# Power.net
KiCad netlist of a schematic drawn in Altium Designer
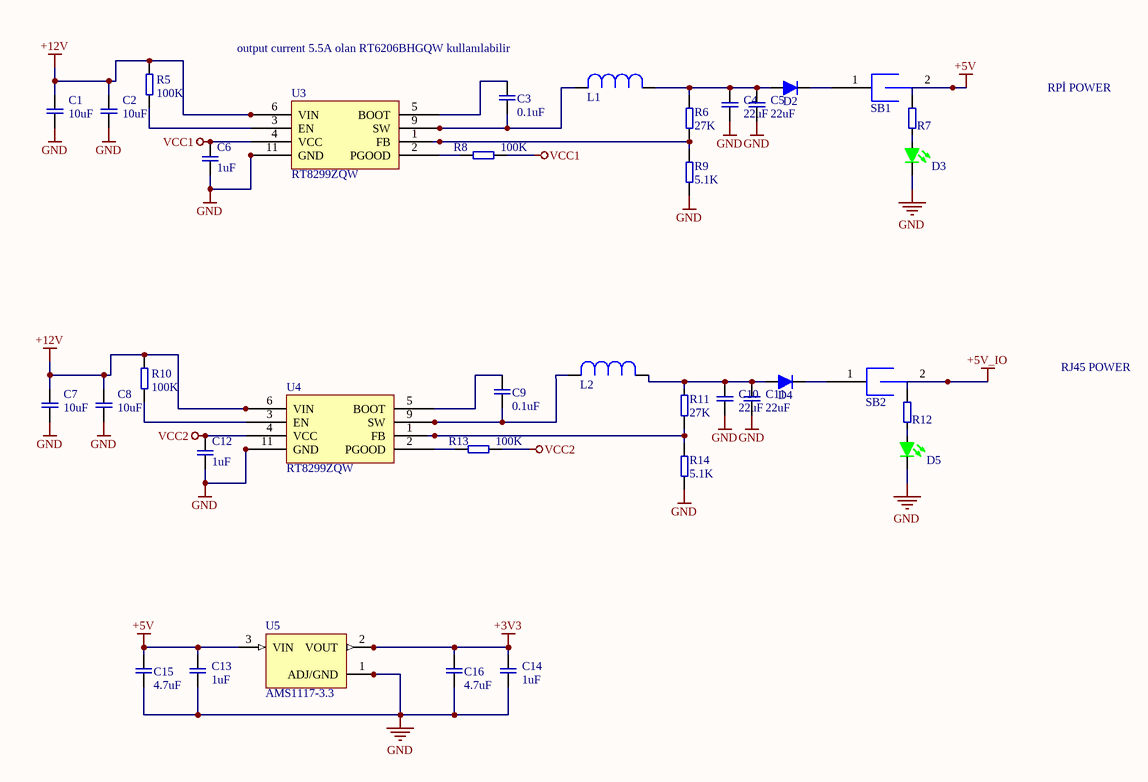
[diagram p0: Power.SchDoc]

(export (version "E")
  (design (tool "Eeschema 10.0.6"))
  (components
    (comp (ref "C1")
      (value "10uF")
      (footprint "C0805")
      (description "CAP CER 10UF 25V X5R 0805")
      (fields (field (name "PART NUMBER") "CC0805KKX5R8BB106") (field (name "VOLTAGE") "25V"))
      (libsource (lib "anayurt") (part "CAP"))
    )
    (comp (ref "C2")
      (value "10uF")
      (footprint "C0805")
      (description "CAP CER 10UF 25V X5R 0805")
      (fields (field (name "PART NUMBER") "CC0805KKX5R8BB106") (field (name "VOLTAGE") "25V"))
      (libsource (lib "anayurt") (part "CAP"))
    )
    (comp (ref "C3")
      (value "0.1uF")
      (footprint "C0402")
      (description "CAP CER 0.1UF 25V X7R 0402")
      (fields (field (name "PART NUMBER") "04023C104KAT2A") (field (name "VOLTAGE") "25V"))
      (libsource (lib "anayurt") (part "CAP"))
    )
    (comp (ref "C4")
      (value "22uF")
      (footprint "C1210")
      (description "CAP CER 22UF 25V X5R 1210")
      (fields (field (name "PART NUMBER") "CL32A226KAJNNWE") (field (name "VOLTAGE") "25V"))
      (libsource (lib "anayurt") (part "CAP"))
    )
    (comp (ref "C5")
      (value "22uF")
      (footprint "C1210")
      (description "CAP CER 22UF 25V X5R 1210")
      (fields (field (name "PART NUMBER") "CL32A226KAJNNWE") (field (name "VOLTAGE") "25V"))
      (libsource (lib "anayurt") (part "CAP"))
    )
    (comp (ref "C6")
      (value "1uF")
      (footprint "C0603")
      (description "CAP CER 1UF 25V X7R 0603")
      (fields (field (name "PART NUMBER") "CGA3E1X7R1E105M080AC") (field (name "VOLTAGE") "25V"))
      (libsource (lib "anayurt") (part "CAP"))
    )
    (comp (ref "C7")
      (value "10uF")
      (footprint "C0805")
      (description "CAP CER 10UF 25V X5R 0805")
      (fields (field (name "PART NUMBER") "CC0805KKX5R8BB106") (field (name "VOLTAGE") "25V"))
      (libsource (lib "anayurt") (part "CAP"))
    )
    (comp (ref "C8")
      (value "10uF")
      (footprint "C0805")
      (description "CAP CER 10UF 25V X5R 0805")
      (fields (field (name "PART NUMBER") "CC0805KKX5R8BB106") (field (name "VOLTAGE") "25V"))
      (libsource (lib "anayurt") (part "CAP"))
    )
    (comp (ref "C9")
      (value "0.1uF")
      (footprint "C0402")
      (description "CAP CER 0.1UF 25V X7R 0402")
      (fields (field (name "PART NUMBER") "04023C104KAT2A") (field (name "VOLTAGE") "25V"))
      (libsource (lib "anayurt") (part "CAP"))
    )
    (comp (ref "C10")
      (value "22uF")
      (footprint "C1210")
      (description "CAP CER 22UF 25V X5R 1210")
      (fields (field (name "PART NUMBER") "CL32A226KAJNNWE") (field (name "VOLTAGE") "25V"))
      (libsource (lib "anayurt") (part "CAP"))
    )
    (comp (ref "C11")
      (value "22uF")
      (footprint "C1210")
      (description "CAP CER 22UF 25V X5R 1210")
      (fields (field (name "PART NUMBER") "CL32A226KAJNNWE") (field (name "VOLTAGE") "25V"))
      (libsource (lib "anayurt") (part "CAP"))
    )
    (comp (ref "C12")
      (value "1uF")
      (footprint "C0603")
      (description "CAP CER 1UF 25V X7R 0603")
      (fields (field (name "PART NUMBER") "CGA3E1X7R1E105M080AC") (field (name "VOLTAGE") "25V"))
      (libsource (lib "anayurt") (part "CAP"))
    )
    (comp (ref "C13")
      (value "1uF")
      (footprint "C0402")
      (description "CAP CER 1UF 16V X5R 0402")
      (fields (field (name "PART NUMBER") "CL05A105KO5NNNC") (field (name "VOLTAGE") "16V"))
      (libsource (lib "anayurt") (part "CAP"))
    )
    (comp (ref "C14")
      (value "1uF")
      (footprint "C0402")
      (description "CAP CER 1UF 16V X5R 0402")
      (fields (field (name "PART NUMBER") "CL05A105KO5NNNC") (field (name "VOLTAGE") "16V"))
      (libsource (lib "anayurt") (part "CAP"))
    )
    (comp (ref "C15")
      (value "4.7uF")
      (footprint "C0402")
      (description "CAP CER 4.7UF 10V X5R 0402")
      (fields (field (name "PART NUMBER") "C1005X5R1A475K050BC") (field (name "VOLTAGE") "10V"))
      (libsource (lib "anayurt") (part "CAP"))
    )
    (comp (ref "C16")
      (value "4.7uF")
      (footprint "C0402")
      (description "CAP CER 4.7UF 10V X5R 0402")
      (fields (field (name "PART NUMBER") "C1005X5R1A475K050BC") (field (name "VOLTAGE") "10V"))
      (libsource (lib "anayurt") (part "CAP"))
    )
    (comp (ref "D2")
      (value "TSSA3U60 R3G")
      (footprint "TAIWAN_TSSA3U60 R3G")
      (description "DIODE SCHOTTKY 60V 3A DO214AC")
      (fields (field (name "MANUFACTURER") "Taiwan Semiconductor Corporation"))
      (libsource (lib "anayurt") (part "DIODE"))
    )
    (comp (ref "D3")
      (value "SML-LX0603GW-TR")
      (footprint "L0603")
      (description "LED GREEN DIFFUSED SMD")
      (fields (field (name "MANUFACTURER") "Lumex Opto/Components Inc."))
      (libsource (lib "anayurt") (part "LED_GREEN"))
    )
    (comp (ref "D4")
      (value "TSSA3U60 R3G")
      (footprint "TAIWAN_TSSA3U60 R3G")
      (description "DIODE SCHOTTKY 60V 3A DO214AC")
      (fields (field (name "MANUFACTURER") "Taiwan Semiconductor Corporation"))
      (libsource (lib "anayurt") (part "DIODE"))
    )
    (comp (ref "D5")
      (value "SML-LX0603GW-TR")
      (footprint "L0603")
      (description "LED GREEN DIFFUSED SMD")
      (fields (field (name "MANUFACTURER") "Lumex Opto/Components Inc."))
      (libsource (lib "anayurt") (part "LED_GREEN"))
    )
    (comp (ref "L1")
      (value "XAL6060-682MEB")
      (footprint "CC_XAL6060-682MEB")
      (description "6.8uH 9A 20.8mOhm Inductor")
      (fields (field (name "MANUFACTURER") "Coilcraft"))
      (libsource (lib "anayurt") (part "PINDC"))
    )
    (comp (ref "L2")
      (value "XAL6060-682MEB")
      (footprint "CC_XAL6060-682MEB")
      (description "6.8uH 9A 20.8mOhm Inductor")
      (fields (field (name "MANUFACTURER") "Coilcraft"))
      (libsource (lib "anayurt") (part "PINDC"))
    )
    (comp (ref "R5")
      (value "100K")
      (footprint "R0402")
      (description "RES SMD 100K OHM 1% 1/16W 0402")
      (fields (field (name "PART NUMBER") "RC0402FR-07100KL") (field (name "TOLERANCE") "1%"))
      (libsource (lib "anayurt") (part "RES"))
    )
    (comp (ref "R6")
      (value "27K")
      (footprint "R0402")
      (description "RES 27K OHM 1% 1/16W 0402")
      (fields (field (name "PART NUMBER") "RMCF0402FT27K0") (field (name "TOLERANCE") "±1%"))
      (libsource (lib "anayurt") (part "RES"))
    )
    (comp (ref "R7")
      (value "330R")
      (footprint "R0603")
      (description "RES 330 OHM 1% 1/10W 0603")
      (fields (field (name "PART NUMBER") "RMCF0603FT330R") (field (name "TOLERANCE") "0.1%"))
      (libsource (lib "anayurt") (part "RES"))
    )
    (comp (ref "R8")
      (value "100K")
      (footprint "R0402")
      (description "RES SMD 100K OHM 1% 1/16W 0402")
      (fields (field (name "PART NUMBER") "RC0402FR-07100KL") (field (name "TOLERANCE") "1%"))
      (libsource (lib "anayurt") (part "RES"))
    )
    (comp (ref "R9")
      (value "5.1K")
      (footprint "R0402")
      (description "RES 5.1K OHM 1% 1/16W 0402")
      (fields (field (name "PART NUMBER") "RC0402FR-075K1L") (field (name "TOLERANCE") "1%"))
      (libsource (lib "anayurt") (part "RES"))
    )
    (comp (ref "R10")
      (value "100K")
      (footprint "R0402")
      (description "RES SMD 100K OHM 1% 1/16W 0402")
      (fields (field (name "PART NUMBER") "RC0402FR-07100KL") (field (name "TOLERANCE") "1%"))
      (libsource (lib "anayurt") (part "RES"))
    )
    (comp (ref "R11")
      (value "27K")
      (footprint "R0402")
      (description "RES 27K OHM 1% 1/16W 0402")
      (fields (field (name "PART NUMBER") "RMCF0402FT27K0") (field (name "TOLERANCE") "±1%"))
      (libsource (lib "anayurt") (part "RES"))
    )
    (comp (ref "R12")
      (value "330R")
      (footprint "R0603")
      (description "RES 330 OHM 1% 1/10W 0603")
      (fields (field (name "PART NUMBER") "RMCF0603FT330R") (field (name "TOLERANCE") "0.1%"))
      (libsource (lib "anayurt") (part "RES"))
    )
    (comp (ref "R13")
      (value "100K")
      (footprint "R0402")
      (description "RES SMD 100K OHM 1% 1/16W 0402")
      (fields (field (name "PART NUMBER") "RC0402FR-07100KL") (field (name "TOLERANCE") "1%"))
      (libsource (lib "anayurt") (part "RES"))
    )
    (comp (ref "R14")
      (value "5.1K")
      (footprint "R0402")
      (description "RES 5.1K OHM 1% 1/16W 0402")
      (fields (field (name "PART NUMBER") "RC0402FR-075K1L") (field (name "TOLERANCE") "1%"))
      (libsource (lib "anayurt") (part "RES"))
    )
    (comp (ref "SB1")
      (value "Jumper")
      (footprint "SB.0805")
      (description "0805 Solder Bridge")
      (fields (field (name "PART NUMBER") "Solder Bridge0805"))
      (libsource (lib "anayurt") (part "Bridge"))
    )
    (comp (ref "SB2")
      (value "Jumper")
      (footprint "SB.0805")
      (description "0805 Solder Bridge")
      (fields (field (name "PART NUMBER") "Solder Bridge0805"))
      (libsource (lib "anayurt") (part "Bridge"))
    )
    (comp (ref "U3")
      (value "RT8299ZQW")
      (footprint "RT8299ZQW")
      (description "IC REG BUCK ADJUSTABLE 3A 10WDFN")
      (fields (field (name "MANUFACTURER") "Richtek USA Inc."))
      (libsource (lib "anayurt") (part "RT8299ZQW"))
    )
    (comp (ref "U4")
      (value "RT8299ZQW")
      (footprint "RT8299ZQW")
      (description "IC REG BUCK ADJUSTABLE 3A 10WDFN")
      (fields (field (name "MANUFACTURER") "Richtek USA Inc."))
      (libsource (lib "anayurt") (part "RT8299ZQW"))
    )
    (comp (ref "U5")
      (value "AMS1117-3.3")
      (footprint "AMS1117-3.3")
      (description "IC-1117 V.REG. 1A 3V3 SOT223 SMD AMS")
      (fields (field (name "MANUFACTURER") "AMS"))
      (libsource (lib "anayurt") (part "AMS1117-3.3"))
    )
  )
  (nets
    (net (code "1") (name "+3V3") (class "Default")
      (node (ref "C14") (pin "2") (pinfunction "2_2") (pintype "passive"))
      (node (ref "C16") (pin "2") (pinfunction "2_2") (pintype "passive"))
      (node (ref "U5") (pin "2") (pinfunction "VOUT_2") (pintype "output"))
    )
    (net (code "2") (name "+5V") (class "Default")
      (node (ref "C13") (pin "2") (pinfunction "2_2") (pintype "passive"))
      (node (ref "C15") (pin "2") (pinfunction "2_2") (pintype "passive"))
      (node (ref "R7") (pin "2") (pinfunction "2_2") (pintype "passive"))
      (node (ref "SB1") (pin "2") (pinfunction "2_2") (pintype "passive"))
      (node (ref "U5") (pin "3") (pinfunction "VIN_3") (pintype "input"))
    )
    (net (code "3") (name "+5V_IO") (class "Default")
      (node (ref "R12") (pin "2") (pinfunction "2_2") (pintype "passive"))
      (node (ref "SB2") (pin "2") (pinfunction "2_2") (pintype "passive"))
    )
    (net (code "4") (name "+12V") (class "Default")
      (node (ref "C1") (pin "1") (pinfunction "1_1") (pintype "passive"))
      (node (ref "C2") (pin "1") (pinfunction "1_1") (pintype "passive"))
      (node (ref "C7") (pin "1") (pinfunction "1_1") (pintype "passive"))
      (node (ref "C8") (pin "1") (pinfunction "1_1") (pintype "passive"))
      (node (ref "R10") (pin "2") (pinfunction "2_2") (pintype "passive"))
      (node (ref "R5") (pin "2") (pinfunction "2_2") (pintype "passive"))
      (node (ref "U3") (pin "6") (pinfunction "VIN_6") (pintype "passive"))
      (node (ref "U3") (pin "7") (pinfunction "VIN_7") (pintype "passive"))
      (node (ref "U4") (pin "6") (pinfunction "VIN_6") (pintype "passive"))
      (node (ref "U4") (pin "7") (pinfunction "VIN_7") (pintype "passive"))
    )
    (net (code "5") (name "GND") (class "Default")
      (node (ref "C1") (pin "2") (pinfunction "2_2") (pintype "passive"))
      (node (ref "C10") (pin "1") (pinfunction "1_1") (pintype "passive"))
      (node (ref "C11") (pin "1") (pinfunction "1_1") (pintype "passive"))
      (node (ref "C12") (pin "1") (pinfunction "1_1") (pintype "passive"))
      (node (ref "C13") (pin "1") (pinfunction "1_1") (pintype "passive"))
      (node (ref "C14") (pin "1") (pinfunction "1_1") (pintype "passive"))
      (node (ref "C15") (pin "1") (pinfunction "1_1") (pintype "passive"))
      (node (ref "C16") (pin "1") (pinfunction "1_1") (pintype "passive"))
      (node (ref "C2") (pin "2") (pinfunction "2_2") (pintype "passive"))
      (node (ref "C4") (pin "1") (pinfunction "1_1") (pintype "passive"))
      (node (ref "C5") (pin "1") (pinfunction "1_1") (pintype "passive"))
      (node (ref "C6") (pin "1") (pinfunction "1_1") (pintype "passive"))
      (node (ref "C7") (pin "2") (pinfunction "2_2") (pintype "passive"))
      (node (ref "C8") (pin "2") (pinfunction "2_2") (pintype "passive"))
      (node (ref "D3") (pin "C") (pinfunction "C_C") (pintype "passive"))
      (node (ref "D5") (pin "C") (pinfunction "C_C") (pintype "passive"))
      (node (ref "R14") (pin "2") (pinfunction "2_2") (pintype "passive"))
      (node (ref "R9") (pin "2") (pinfunction "2_2") (pintype "passive"))
      (node (ref "U3") (pin "10") (pinfunction "GND_10") (pintype "passive"))
      (node (ref "U3") (pin "11") (pinfunction "GND_11") (pintype "passive"))
      (node (ref "U4") (pin "10") (pinfunction "GND_10") (pintype "passive"))
      (node (ref "U4") (pin "11") (pinfunction "GND_11") (pintype "passive"))
      (node (ref "U5") (pin "1") (pinfunction "ADJ/GND_1") (pintype "power_in"))
    )
    (net (code "6") (name "Net-(C3-Pad1)") (class "Default")
      (node (ref "C3") (pin "1") (pinfunction "1_1") (pintype "passive"))
      (node (ref "L1") (pin "2") (pinfunction "2_2") (pintype "passive"))
      (node (ref "U3") (pin "8") (pinfunction "SW_8") (pintype "passive"))
      (node (ref "U3") (pin "9") (pinfunction "SW_9") (pintype "passive"))
    )
    (net (code "7") (name "Net-(C4-Pad2)") (class "Default")
      (node (ref "C4") (pin "2") (pinfunction "2_2") (pintype "passive"))
      (node (ref "C5") (pin "2") (pinfunction "2_2") (pintype "passive"))
      (node (ref "D2") (pin "A") (pinfunction "A_A") (pintype "passive"))
      (node (ref "L1") (pin "1") (pinfunction "1_1") (pintype "passive"))
      (node (ref "R6") (pin "2") (pinfunction "2_2") (pintype "passive"))
    )
    (net (code "8") (name "Net-(C9-Pad1)") (class "Default")
      (node (ref "C9") (pin "1") (pinfunction "1_1") (pintype "passive"))
      (node (ref "L2") (pin "2") (pinfunction "2_2") (pintype "passive"))
      (node (ref "U4") (pin "8") (pinfunction "SW_8") (pintype "passive"))
      (node (ref "U4") (pin "9") (pinfunction "SW_9") (pintype "passive"))
    )
    (net (code "9") (name "Net-(C10-Pad2)") (class "Default")
      (node (ref "C10") (pin "2") (pinfunction "2_2") (pintype "passive"))
      (node (ref "C11") (pin "2") (pinfunction "2_2") (pintype "passive"))
      (node (ref "D4") (pin "A") (pinfunction "A_A") (pintype "passive"))
      (node (ref "L2") (pin "1") (pinfunction "1_1") (pintype "passive"))
      (node (ref "R11") (pin "2") (pinfunction "2_2") (pintype "passive"))
    )
    (net (code "10") (name "Net-(D2-PadC)") (class "Default")
      (node (ref "D2") (pin "C") (pinfunction "C_C") (pintype "passive"))
      (node (ref "SB1") (pin "1") (pinfunction "1_1") (pintype "passive"))
    )
    (net (code "11") (name "Net-(D3-PadA)") (class "Default")
      (node (ref "D3") (pin "A") (pinfunction "A_A") (pintype "passive"))
      (node (ref "R7") (pin "1") (pinfunction "1_1") (pintype "passive"))
    )
    (net (code "12") (name "Net-(D4-PadC)") (class "Default")
      (node (ref "D4") (pin "C") (pinfunction "C_C") (pintype "passive"))
      (node (ref "SB2") (pin "1") (pinfunction "1_1") (pintype "passive"))
    )
    (net (code "13") (name "Net-(D5-PadA)") (class "Default")
      (node (ref "D5") (pin "A") (pinfunction "A_A") (pintype "passive"))
      (node (ref "R12") (pin "1") (pinfunction "1_1") (pintype "passive"))
    )
    (net (code "14") (name "Net-(U3-BOOT)") (class "Default")
      (node (ref "C3") (pin "2") (pinfunction "2_2") (pintype "passive"))
      (node (ref "U3") (pin "5") (pinfunction "BOOT_5") (pintype "passive"))
    )
    (net (code "15") (name "Net-(U3-EN)") (class "Default")
      (node (ref "R5") (pin "1") (pinfunction "1_1") (pintype "passive"))
      (node (ref "U3") (pin "3") (pinfunction "EN_3") (pintype "passive"))
    )
    (net (code "16") (name "Net-(U3-FB)") (class "Default")
      (node (ref "R6") (pin "1") (pinfunction "1_1") (pintype "passive"))
      (node (ref "R9") (pin "1") (pinfunction "1_1") (pintype "passive"))
      (node (ref "U3") (pin "1") (pinfunction "FB_1") (pintype "passive"))
    )
    (net (code "17") (name "Net-(U3-PGOOD)") (class "Default")
      (node (ref "R8") (pin "2") (pinfunction "2_2") (pintype "passive"))
      (node (ref "U3") (pin "2") (pinfunction "PGOOD_2") (pintype "power_in"))
    )
    (net (code "18") (name "Net-(U4-BOOT)") (class "Default")
      (node (ref "C9") (pin "2") (pinfunction "2_2") (pintype "passive"))
      (node (ref "U4") (pin "5") (pinfunction "BOOT_5") (pintype "passive"))
    )
    (net (code "19") (name "Net-(U4-EN)") (class "Default")
      (node (ref "R10") (pin "1") (pinfunction "1_1") (pintype "passive"))
      (node (ref "U4") (pin "3") (pinfunction "EN_3") (pintype "passive"))
    )
    (net (code "20") (name "Net-(U4-FB)") (class "Default")
      (node (ref "R11") (pin "1") (pinfunction "1_1") (pintype "passive"))
      (node (ref "R14") (pin "1") (pinfunction "1_1") (pintype "passive"))
      (node (ref "U4") (pin "1") (pinfunction "FB_1") (pintype "passive"))
    )
    (net (code "21") (name "Net-(U4-PGOOD)") (class "Default")
      (node (ref "R13") (pin "2") (pinfunction "2_2") (pintype "passive"))
      (node (ref "U4") (pin "2") (pinfunction "PGOOD_2") (pintype "power_in"))
    )
    (net (code "22") (name "VCC1") (class "Default")
      (node (ref "C6") (pin "2") (pinfunction "2_2") (pintype "passive"))
      (node (ref "R8") (pin "1") (pinfunction "1_1") (pintype "passive"))
      (node (ref "U3") (pin "4") (pinfunction "VCC_4") (pintype "power_in"))
    )
    (net (code "23") (name "VCC2") (class "Default")
      (node (ref "C12") (pin "2") (pinfunction "2_2") (pintype "passive"))
      (node (ref "R13") (pin "1") (pinfunction "1_1") (pintype "passive"))
      (node (ref "U4") (pin "4") (pinfunction "VCC_4") (pintype "power_in"))
    )
  )
)
